# Front_left_lamp_v4B.net
KiCad netlist of a schematic drawn in EAGLE
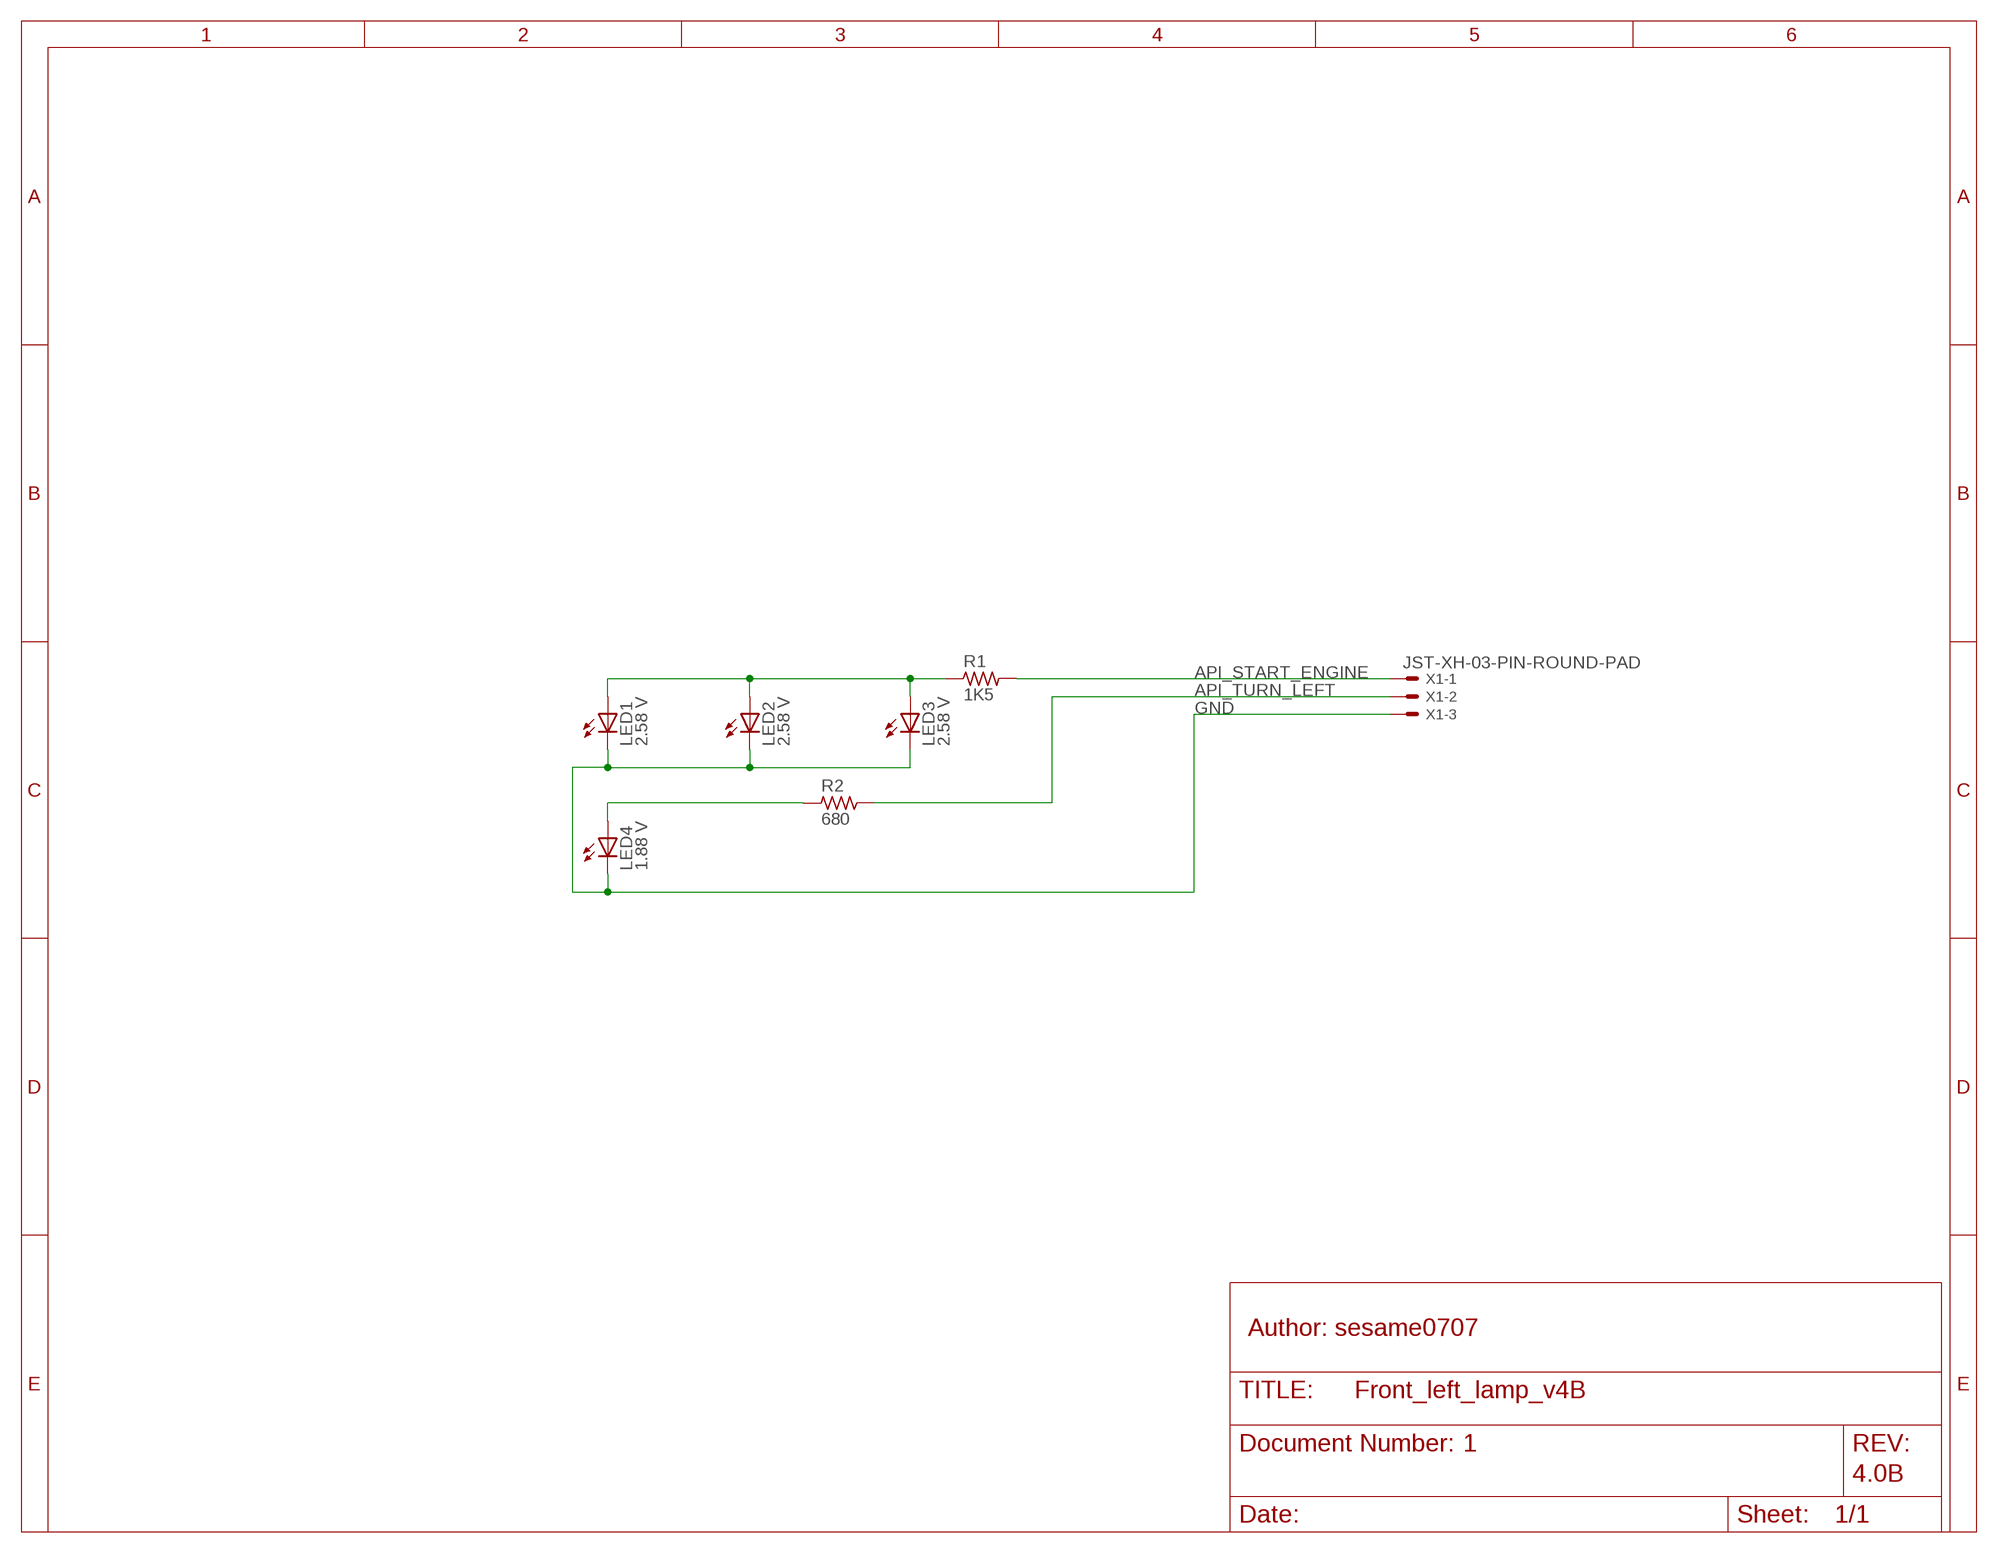
[diagram p0: schematic, sheet 1]

(export (version "E")
  (design (tool "Eeschema 10.0.6"))
  (components
    (comp (ref "LED1")
      (value "2.58 V")
      (footprint "eagle-import:LED5MM")
      (libsource (lib "eagle-import") (part "LED5MM"))
    )
    (comp (ref "LED2")
      (value "2.58 V")
      (footprint "eagle-import:LED5MM")
      (libsource (lib "eagle-import") (part "LED5MM"))
    )
    (comp (ref "LED3")
      (value "2.58 V")
      (footprint "eagle-import:LED5MM")
      (libsource (lib "eagle-import") (part "LED5MM"))
    )
    (comp (ref "LED4")
      (value "1.88 V")
      (footprint "eagle-import:LED5MM")
      (libsource (lib "eagle-import") (part "LED5MM"))
    )
    (comp (ref "R1")
      (value "1K5")
      (footprint "eagle-import:R1206")
      (libsource (lib "eagle-import") (part "R_1206"))
    )
    (comp (ref "R2")
      (value "680")
      (footprint "eagle-import:R1206")
      (libsource (lib "eagle-import") (part "R_1206"))
    )
    (comp (ref "X1")
      (value "JST-XH-03-PIN-ROUND-PAD")
      (footprint "eagle-import:JST-XH-03-PACKAGE-ROUND-PAD")
      (libsource (lib "eagle-import") (part "JST-XH-03-PIN-ROUND-PAD"))
    )
  )
  (nets
    (net (code "1") (name "/API_START_ENGINE") (class "Default")
      (node (ref "LED1") (pin "A") (pinfunction "A_A") (pintype "passive"))
      (node (ref "LED2") (pin "A") (pinfunction "A_A") (pintype "passive"))
      (node (ref "LED3") (pin "A") (pinfunction "A_A") (pintype "passive"))
      (node (ref "R1") (pin "1") (pinfunction "1_1") (pintype "passive"))
    )
    (net (code "2") (name "/API_TURN_LEFT") (class "Default")
      (node (ref "R2") (pin "2") (pinfunction "2_2") (pintype "passive"))
      (node (ref "X1") (pin "2") (pinfunction "S_2") (pintype "passive"))
    )
    (net (code "3") (name "/GND") (class "Default")
      (node (ref "LED1") (pin "K") (pinfunction "C_K") (pintype "passive"))
      (node (ref "LED2") (pin "K") (pinfunction "C_K") (pintype "passive"))
      (node (ref "LED3") (pin "K") (pinfunction "C_K") (pintype "passive"))
      (node (ref "LED4") (pin "K") (pinfunction "C_K") (pintype "passive"))
      (node (ref "X1") (pin "3") (pinfunction "S_3") (pintype "passive"))
    )
    (net (code "4") (name "Net-(LED4-PadA)") (class "Default")
      (node (ref "LED4") (pin "A") (pinfunction "A_A") (pintype "passive"))
      (node (ref "R2") (pin "1") (pinfunction "1_1") (pintype "passive"))
    )
    (net (code "5") (name "Net-(X1A-S)") (class "Default")
      (node (ref "R1") (pin "2") (pinfunction "2_2") (pintype "passive"))
      (node (ref "X1") (pin "1") (pinfunction "S_1") (pintype "passive"))
    )
  )
)
